# PET_Diag_Clip.net
KiCad netlist of a schematic drawn in EAGLE
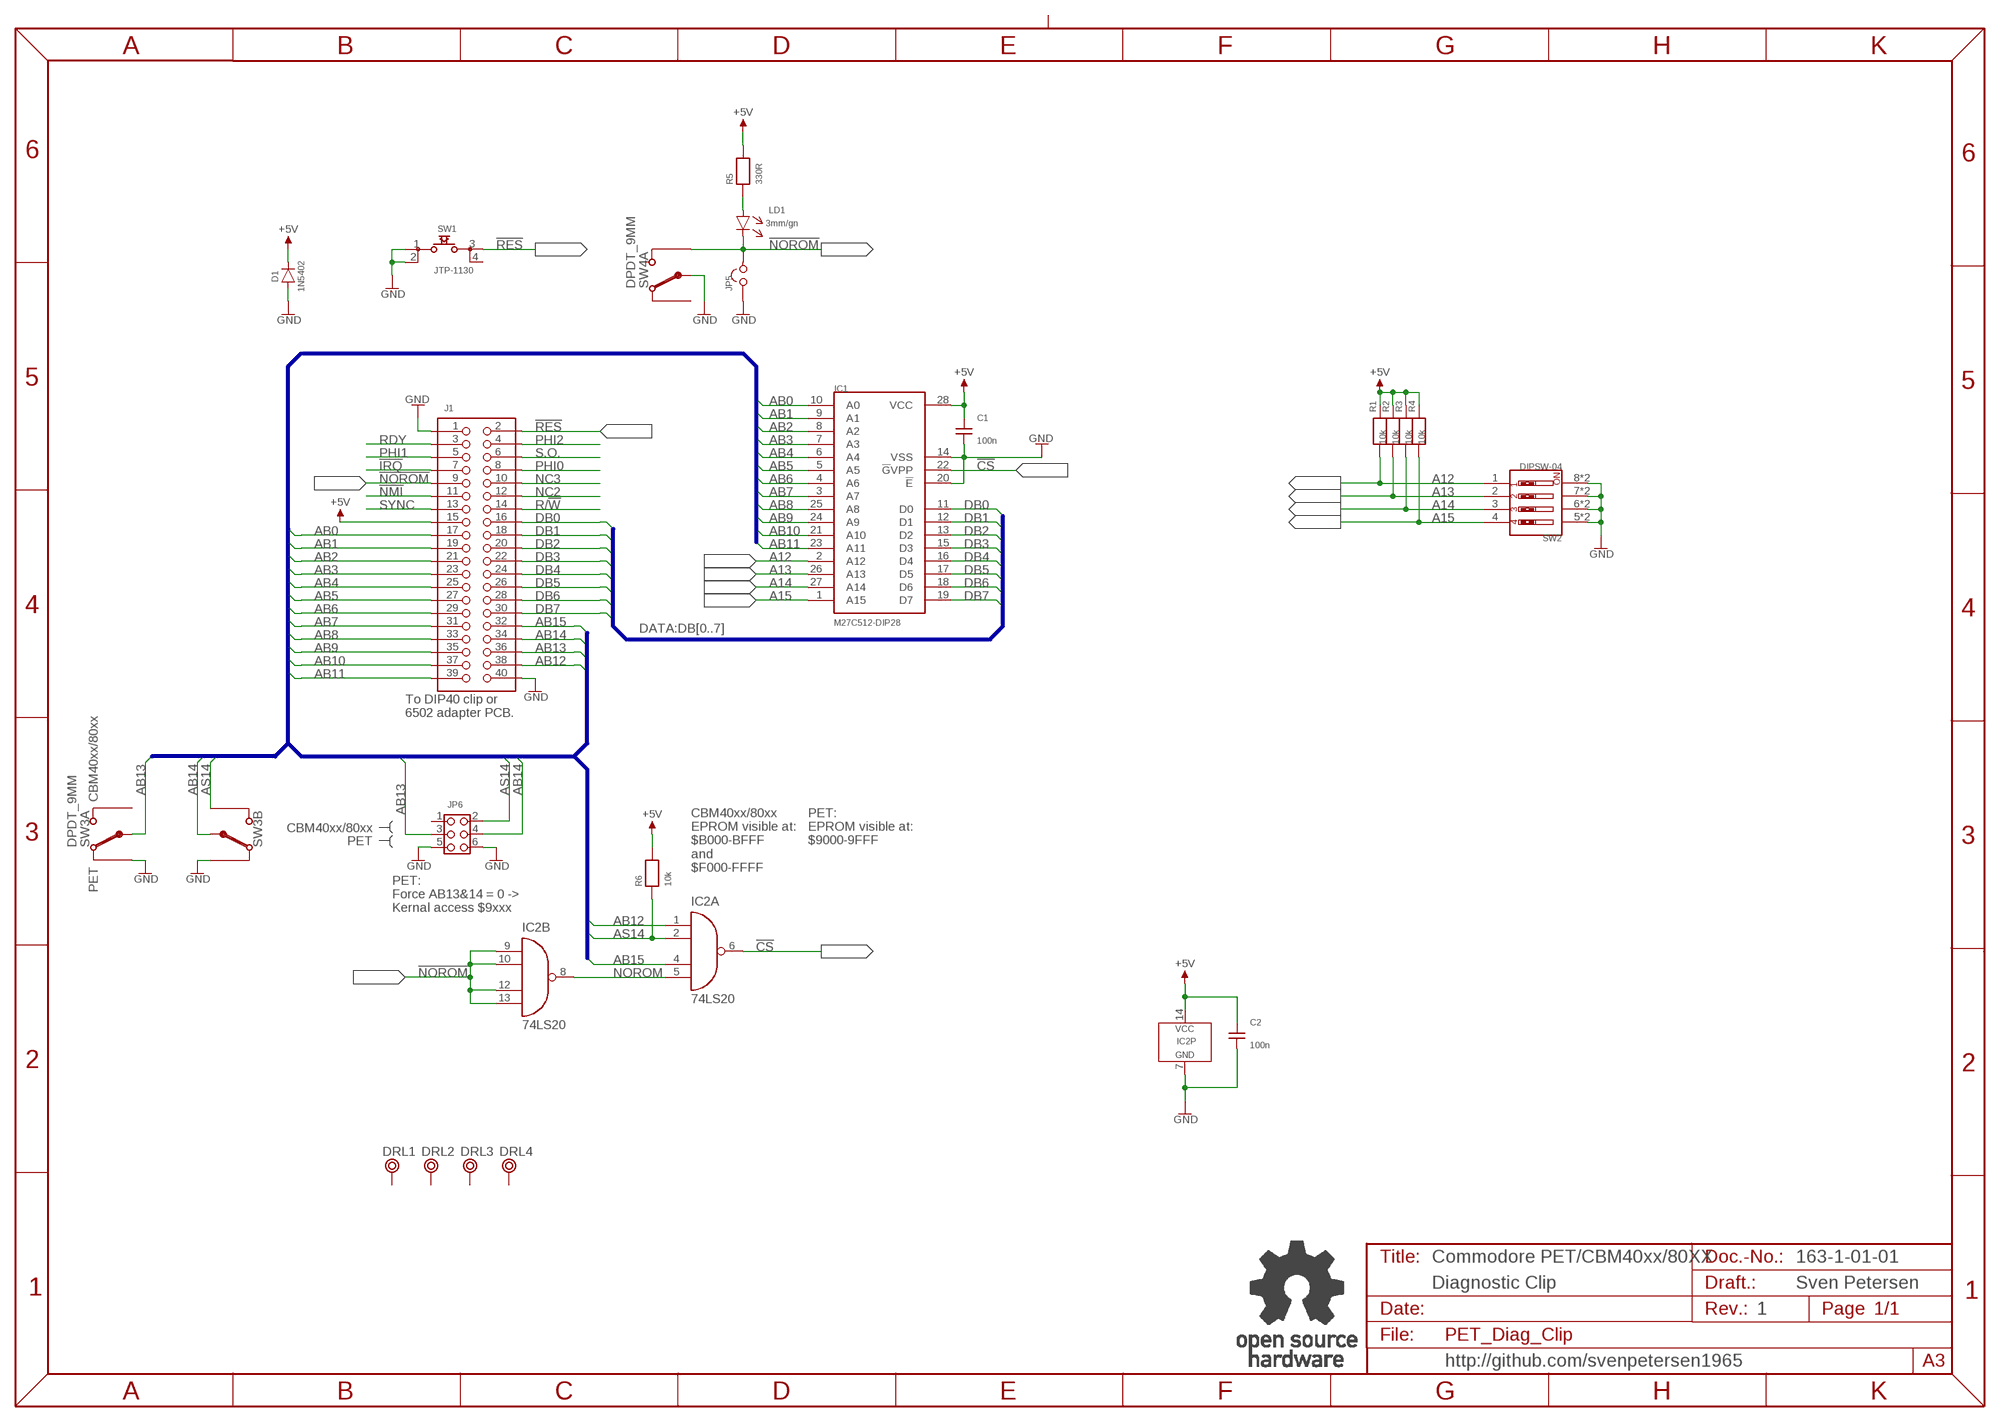
[diagram p0: schematic, sheet 1]

(export (version "E")
  (design (tool "Eeschema 10.0.6"))
  (components
    (comp (ref "C1")
      (value "100n")
      (footprint "eagle-import:C-2,5")
      (libsource (lib "eagle-import") (part "CAP01"))
    )
    (comp (ref "C2")
      (value "100n")
      (footprint "eagle-import:C-2,5")
      (libsource (lib "eagle-import") (part "CAP01"))
    )
    (comp (ref "D1")
      (value "1N5402")
      (footprint "eagle-import:DO-201")
      (libsource (lib "eagle-import") (part "1N5402"))
    )
    (comp (ref "DRL1")
      (value "BOHR3,5")
      (footprint "eagle-import:BOHR3,5")
      (libsource (lib "eagle-import") (part "BOHR3,5"))
    )
    (comp (ref "DRL2")
      (value "BOHR3,5")
      (footprint "eagle-import:BOHR3,5")
      (libsource (lib "eagle-import") (part "BOHR3,5"))
    )
    (comp (ref "DRL3")
      (value "BOHR3,5")
      (footprint "eagle-import:BOHR3,5")
      (libsource (lib "eagle-import") (part "BOHR3,5"))
    )
    (comp (ref "DRL4")
      (value "BOHR3,5")
      (footprint "eagle-import:BOHR3,5")
      (libsource (lib "eagle-import") (part "BOHR3,5"))
    )
    (comp (ref "IC1")
      (value "M27C512-DIP28")
      (footprint "eagle-import:DIL28-6")
      (libsource (lib "eagle-import") (part "M27C512-DIP28"))
    )
    (comp (ref "IC2")
      (value "74LS20")
      (footprint "eagle-import:DIL-14")
      (libsource (lib "eagle-import") (part "7420N"))
    )
    (comp (ref "J1")
      (value "PINHD-2X20WV")
      (footprint "eagle-import:2X20WV")
      (libsource (lib "eagle-import") (part "PINHD-2X20WV"))
    )
    (comp (ref "JP5")
      (value "JUMPER")
      (footprint "eagle-import:1X02")
      (libsource (lib "eagle-import") (part "JUMPER"))
    )
    (comp (ref "JP6")
      (value "JUMPER2X3")
      (footprint "eagle-import:2X03")
      (libsource (lib "eagle-import") (part "JUMPER2X3"))
    )
    (comp (ref "LD1")
      (value "3mm/gn")
      (footprint "eagle-import:3MM")
      (libsource (lib "eagle-import") (part "3MM"))
    )
    (comp (ref "R1")
      (value "10k")
      (footprint "eagle-import:R-10")
      (libsource (lib "eagle-import") (part "RES04"))
    )
    (comp (ref "R2")
      (value "10k")
      (footprint "eagle-import:R-10")
      (libsource (lib "eagle-import") (part "RES04"))
    )
    (comp (ref "R3")
      (value "10k")
      (footprint "eagle-import:R-10")
      (libsource (lib "eagle-import") (part "RES04"))
    )
    (comp (ref "R4")
      (value "10k")
      (footprint "eagle-import:R-10")
      (libsource (lib "eagle-import") (part "RES04"))
    )
    (comp (ref "R5")
      (value "330R")
      (footprint "eagle-import:R-10")
      (libsource (lib "eagle-import") (part "RES04"))
    )
    (comp (ref "R6")
      (value "10k")
      (footprint "eagle-import:R-10")
      (libsource (lib "eagle-import") (part "RES04"))
    )
    (comp (ref "SW1")
      (value "JTP-1130")
      (footprint "eagle-import:JTP-1130")
      (libsource (lib "eagle-import") (part "JTP-1130"))
    )
    (comp (ref "SW2")
      (value "DIPSW-04")
      (footprint "eagle-import:DIPSW-04V-COMBI")
      (libsource (lib "eagle-import") (part "DIPSW-04"))
    )
    (comp (ref "SW3")
      (value "DPDT_9MM")
      (footprint "eagle-import:DPDT_9MM")
      (libsource (lib "eagle-import") (part "DPDT_9MM"))
    )
    (comp (ref "SW4")
      (value "DPDT_9MM")
      (footprint "eagle-import:DPDT_9MM")
      (libsource (lib "eagle-import") (part "DPDT_9MM"))
    )
    (comp (ref "U$13")
      (value "OPEN_SOURCE_HW")
      (footprint "eagle-import:OPENHW")
      (libsource (lib "eagle-import") (part "OPEN_SOURCE_HW"))
    )
  )
  (nets
    (net (code "9") (name "+5V") (class "Default")
      (node (ref "C1") (pin "2") (pinfunction "2_2") (pintype "passive"))
      (node (ref "C2") (pin "2") (pinfunction "2_2") (pintype "passive"))
      (node (ref "D1") (pin "K") (pinfunction "K_K") (pintype "passive"))
      (node (ref "IC1") (pin "28") (pinfunction "VCC_28") (pintype "power_in"))
      (node (ref "IC2") (pin "14") (pinfunction "VCC_14") (pintype "bidirectional"))
      (node (ref "J1") (pin "15") (pinfunction "15_15") (pintype "passive"))
      (node (ref "R1") (pin "1") (pinfunction "1_1") (pintype "passive"))
      (node (ref "R2") (pin "1") (pinfunction "1_1") (pintype "passive"))
      (node (ref "R3") (pin "1") (pinfunction "1_1") (pintype "passive"))
      (node (ref "R4") (pin "1") (pinfunction "1_1") (pintype "passive"))
      (node (ref "R5") (pin "2") (pinfunction "2_2") (pintype "passive"))
      (node (ref "R6") (pin "2") (pinfunction "2_2") (pintype "passive"))
    )
    (net (code "10") (name "/A12") (class "Default")
      (node (ref "IC1") (pin "2") (pinfunction "A12_2") (pintype "input"))
      (node (ref "R1") (pin "2") (pinfunction "2_2") (pintype "passive"))
      (node (ref "SW2") (pin "1") (pinfunction "1_1") (pintype "passive"))
    )
    (net (code "11") (name "/A13") (class "Default")
      (node (ref "IC1") (pin "26") (pinfunction "A13_26") (pintype "input"))
      (node (ref "R2") (pin "2") (pinfunction "2_2") (pintype "passive"))
      (node (ref "SW2") (pin "2") (pinfunction "2_2") (pintype "passive"))
    )
    (net (code "12") (name "/A14") (class "Default")
      (node (ref "IC1") (pin "27") (pinfunction "A14_27") (pintype "input"))
      (node (ref "R3") (pin "2") (pinfunction "2_2") (pintype "passive"))
      (node (ref "SW2") (pin "3") (pinfunction "3_3") (pintype "passive"))
    )
    (net (code "13") (name "/A15") (class "Default")
      (node (ref "IC1") (pin "1") (pinfunction "A15_1") (pintype "input"))
      (node (ref "R4") (pin "2") (pinfunction "2_2") (pintype "passive"))
      (node (ref "SW2") (pin "4") (pinfunction "4_4") (pintype "passive"))
    )
    (net (code "14") (name "/AB0") (class "Default")
      (node (ref "IC1") (pin "10") (pinfunction "A0_10") (pintype "input"))
      (node (ref "J1") (pin "17") (pinfunction "17_17") (pintype "passive"))
    )
    (net (code "15") (name "/AB1") (class "Default")
      (node (ref "IC1") (pin "9") (pinfunction "A1_9") (pintype "input"))
      (node (ref "J1") (pin "19") (pinfunction "19_19") (pintype "passive"))
    )
    (net (code "16") (name "/AB2") (class "Default")
      (node (ref "IC1") (pin "8") (pinfunction "A2_8") (pintype "input"))
      (node (ref "J1") (pin "21") (pinfunction "21_21") (pintype "passive"))
    )
    (net (code "17") (name "/AB3") (class "Default")
      (node (ref "IC1") (pin "7") (pinfunction "A3_7") (pintype "input"))
      (node (ref "J1") (pin "23") (pinfunction "23_23") (pintype "passive"))
    )
    (net (code "18") (name "/AB4") (class "Default")
      (node (ref "IC1") (pin "6") (pinfunction "A4_6") (pintype "input"))
      (node (ref "J1") (pin "25") (pinfunction "25_25") (pintype "passive"))
    )
    (net (code "19") (name "/AB5") (class "Default")
      (node (ref "IC1") (pin "5") (pinfunction "A5_5") (pintype "input"))
      (node (ref "J1") (pin "27") (pinfunction "27_27") (pintype "passive"))
    )
    (net (code "20") (name "/AB6") (class "Default")
      (node (ref "IC1") (pin "4") (pinfunction "A6_4") (pintype "input"))
      (node (ref "J1") (pin "29") (pinfunction "29_29") (pintype "passive"))
    )
    (net (code "21") (name "/AB7") (class "Default")
      (node (ref "IC1") (pin "3") (pinfunction "A7_3") (pintype "input"))
      (node (ref "J1") (pin "31") (pinfunction "31_31") (pintype "passive"))
    )
    (net (code "22") (name "/AB8") (class "Default")
      (node (ref "IC1") (pin "25") (pinfunction "A8_25") (pintype "input"))
      (node (ref "J1") (pin "33") (pinfunction "33_33") (pintype "passive"))
    )
    (net (code "23") (name "/AB9") (class "Default")
      (node (ref "IC1") (pin "24") (pinfunction "A9_24") (pintype "input"))
      (node (ref "J1") (pin "35") (pinfunction "35_35") (pintype "passive"))
    )
    (net (code "24") (name "/AB10") (class "Default")
      (node (ref "IC1") (pin "21") (pinfunction "A10_21") (pintype "input"))
      (node (ref "J1") (pin "37") (pinfunction "37_37") (pintype "passive"))
    )
    (net (code "25") (name "/AB11") (class "Default")
      (node (ref "IC1") (pin "23") (pinfunction "A11_23") (pintype "input"))
      (node (ref "J1") (pin "39") (pinfunction "39_39") (pintype "passive"))
    )
    (net (code "26") (name "/AB12") (class "Default")
      (node (ref "IC2") (pin "1") (pinfunction "I0_1") (pintype "input"))
      (node (ref "J1") (pin "38") (pinfunction "38_38") (pintype "passive"))
    )
    (net (code "27") (name "/AB13") (class "Default")
      (node (ref "J1") (pin "36") (pinfunction "36_36") (pintype "passive"))
      (node (ref "JP6") (pin "3") (pinfunction "3_3") (pintype "bidirectional"))
      (node (ref "SW3") (pin "2") (pinfunction "COM_2") (pintype "bidirectional"))
    )
    (net (code "28") (name "/AB14") (class "Default")
      (node (ref "J1") (pin "34") (pinfunction "34_34") (pintype "passive"))
      (node (ref "JP6") (pin "4") (pinfunction "4_4") (pintype "bidirectional"))
      (node (ref "SW3") (pin "5") (pinfunction "COM_5") (pintype "bidirectional"))
    )
    (net (code "29") (name "/AB15") (class "Default")
      (node (ref "IC2") (pin "4") (pinfunction "I2_4") (pintype "input"))
      (node (ref "J1") (pin "32") (pinfunction "32_32") (pintype "passive"))
    )
    (net (code "30") (name "/AS14") (class "Default")
      (node (ref "IC2") (pin "2") (pinfunction "I1_2") (pintype "input"))
      (node (ref "JP6") (pin "2") (pinfunction "2_2") (pintype "bidirectional"))
      (node (ref "R6") (pin "1") (pinfunction "1_1") (pintype "passive"))
      (node (ref "SW3") (pin "6") (pinfunction "UP_6") (pintype "bidirectional"))
    )
    (net (code "32") (name "/DB0") (class "Default")
      (node (ref "IC1") (pin "11") (pinfunction "D0_11") (pintype "bidirectional"))
      (node (ref "J1") (pin "16") (pinfunction "16_16") (pintype "passive"))
    )
    (net (code "33") (name "/DB1") (class "Default")
      (node (ref "IC1") (pin "12") (pinfunction "D1_12") (pintype "bidirectional"))
      (node (ref "J1") (pin "18") (pinfunction "18_18") (pintype "passive"))
    )
    (net (code "34") (name "/DB2") (class "Default")
      (node (ref "IC1") (pin "13") (pinfunction "D2_13") (pintype "bidirectional"))
      (node (ref "J1") (pin "20") (pinfunction "20_20") (pintype "passive"))
    )
    (net (code "35") (name "/DB3") (class "Default")
      (node (ref "IC1") (pin "15") (pinfunction "D3_15") (pintype "bidirectional"))
      (node (ref "J1") (pin "22") (pinfunction "22_22") (pintype "passive"))
    )
    (net (code "36") (name "/DB4") (class "Default")
      (node (ref "IC1") (pin "16") (pinfunction "D4_16") (pintype "bidirectional"))
      (node (ref "J1") (pin "24") (pinfunction "24_24") (pintype "passive"))
    )
    (net (code "37") (name "/DB5") (class "Default")
      (node (ref "IC1") (pin "17") (pinfunction "D5_17") (pintype "bidirectional"))
      (node (ref "J1") (pin "26") (pinfunction "26_26") (pintype "passive"))
    )
    (net (code "38") (name "/DB6") (class "Default")
      (node (ref "IC1") (pin "18") (pinfunction "D6_18") (pintype "bidirectional"))
      (node (ref "J1") (pin "28") (pinfunction "28_28") (pintype "passive"))
    )
    (net (code "39") (name "/DB7") (class "Default")
      (node (ref "IC1") (pin "19") (pinfunction "D7_19") (pintype "bidirectional"))
      (node (ref "J1") (pin "30") (pinfunction "30_30") (pintype "passive"))
    )
    (net (code "40") (name "/NC2") (class "Default")
      (node (ref "J1") (pin "12") (pinfunction "12_12") (pintype "passive"))
    )
    (net (code "41") (name "/NC3") (class "Default")
      (node (ref "J1") (pin "10") (pinfunction "10_10") (pintype "passive"))
    )
    (net (code "42") (name "/NOROM") (class "Default")
      (node (ref "IC2") (pin "5") (pinfunction "I3_5") (pintype "input"))
      (node (ref "IC2") (pin "8") (pinfunction "O_8") (pintype "output"))
    )
    (net (code "43") (name "/PHI0") (class "Default")
      (node (ref "J1") (pin "8") (pinfunction "8_8") (pintype "passive"))
    )
    (net (code "44") (name "/PHI1") (class "Default")
      (node (ref "J1") (pin "5") (pinfunction "5_5") (pintype "passive"))
    )
    (net (code "45") (name "/PHI2") (class "Default")
      (node (ref "J1") (pin "4") (pinfunction "4_4") (pintype "passive"))
    )
    (net (code "46") (name "/RDY") (class "Default")
      (node (ref "J1") (pin "3") (pinfunction "3_3") (pintype "passive"))
    )
    (net (code "47") (name "/R{slash}~{W}") (class "Default")
      (node (ref "J1") (pin "14") (pinfunction "14_14") (pintype "passive"))
    )
    (net (code "48") (name "/S.O.") (class "Default")
      (node (ref "J1") (pin "6") (pinfunction "6_6") (pintype "passive"))
    )
    (net (code "49") (name "/SYNC") (class "Default")
      (node (ref "J1") (pin "13") (pinfunction "13_13") (pintype "passive"))
    )
    (net (code "50") (name "/~{CS}") (class "Default")
      (node (ref "IC1") (pin "22") (pinfunction "~{G}VPP_22") (pintype "input"))
      (node (ref "IC2") (pin "6") (pinfunction "O_6") (pintype "output"))
    )
    (net (code "51") (name "/~{IRQ}") (class "Default")
      (node (ref "J1") (pin "7") (pinfunction "7_7") (pintype "passive"))
    )
    (net (code "52") (name "/~{NMI}") (class "Default")
      (node (ref "J1") (pin "11") (pinfunction "11_11") (pintype "passive"))
    )
    (net (code "53") (name "/~{NOROM}") (class "Default")
      (node (ref "IC2") (pin "10") (pinfunction "I1_10") (pintype "input"))
      (node (ref "IC2") (pin "12") (pinfunction "I2_12") (pintype "input"))
      (node (ref "IC2") (pin "13") (pinfunction "I3_13") (pintype "input"))
      (node (ref "IC2") (pin "9") (pinfunction "I0_9") (pintype "input"))
      (node (ref "J1") (pin "9") (pinfunction "9_9") (pintype "passive"))
      (node (ref "JP5") (pin "2") (pinfunction "2_2") (pintype "bidirectional"))
      (node (ref "LD1") (pin "C") (pinfunction "K_C") (pintype "bidirectional"))
      (node (ref "SW4") (pin "1") (pinfunction "UP_1") (pintype "bidirectional"))
    )
    (net (code "54") (name "/~{RES}") (class "Default")
      (node (ref "J1") (pin "2") (pinfunction "2_2") (pintype "passive"))
      (node (ref "SW1") (pin "3") (pinfunction "3_3") (pintype "passive"))
    )
    (net (code "55") (name "GND") (class "Default")
      (node (ref "C1") (pin "1") (pinfunction "1_1") (pintype "passive"))
      (node (ref "C2") (pin "1") (pinfunction "1_1") (pintype "passive"))
      (node (ref "D1") (pin "A") (pinfunction "A_A") (pintype "passive"))
      (node (ref "IC1") (pin "14") (pinfunction "VSS_14") (pintype "power_in"))
      (node (ref "IC1") (pin "20") (pinfunction "~{E}_20") (pintype "input"))
      (node (ref "IC2") (pin "7") (pinfunction "GND_7") (pintype "bidirectional"))
      (node (ref "J1") (pin "1") (pinfunction "1_1") (pintype "passive"))
      (node (ref "J1") (pin "40") (pinfunction "40_40") (pintype "passive"))
      (node (ref "JP5") (pin "1") (pinfunction "1_1") (pintype "bidirectional"))
      (node (ref "JP6") (pin "5") (pinfunction "5_5") (pintype "bidirectional"))
      (node (ref "JP6") (pin "6") (pinfunction "6_6") (pintype "bidirectional"))
      (node (ref "SW1") (pin "1") (pinfunction "1_1") (pintype "passive"))
      (node (ref "SW1") (pin "2") (pinfunction "2_2") (pintype "passive"))
      (node (ref "SW2") (pin "5") (pinfunction "5_5") (pintype "passive"))
      (node (ref "SW2") (pin "5A") (pinfunction "5_5A") (pintype "passive"))
      (node (ref "SW2") (pin "6") (pinfunction "6_6") (pintype "passive"))
      (node (ref "SW2") (pin "6A") (pinfunction "6_6A") (pintype "passive"))
      (node (ref "SW2") (pin "7") (pinfunction "7_7") (pintype "passive"))
      (node (ref "SW2") (pin "7A") (pinfunction "7_7A") (pintype "passive"))
      (node (ref "SW2") (pin "8") (pinfunction "8_8") (pintype "passive"))
      (node (ref "SW2") (pin "8A") (pinfunction "8_8A") (pintype "passive"))
      (node (ref "SW3") (pin "3") (pinfunction "DWN_3") (pintype "bidirectional"))
      (node (ref "SW3") (pin "4") (pinfunction "DWN_4") (pintype "bidirectional"))
      (node (ref "SW4") (pin "2") (pinfunction "COM_2") (pintype "bidirectional"))
    )
    (net (code "56") (name "Net-(LD1-PadA)") (class "Default")
      (node (ref "LD1") (pin "A") (pinfunction "A_A") (pintype "bidirectional"))
      (node (ref "R5") (pin "1") (pinfunction "1_1") (pintype "passive"))
    )
    (net (code "57") (name "unconnected-(DRL1-PadP$1)") (class "Default")
      (node (ref "DRL1") (pin "P$1") (pinfunction "P$1_P$1") (pintype "passive"))
    )
    (net (code "58") (name "unconnected-(DRL2-PadP$1)") (class "Default")
      (node (ref "DRL2") (pin "P$1") (pinfunction "P$1_P$1") (pintype "passive"))
    )
    (net (code "59") (name "unconnected-(DRL3-PadP$1)") (class "Default")
      (node (ref "DRL3") (pin "P$1") (pinfunction "P$1_P$1") (pintype "passive"))
    )
    (net (code "60") (name "unconnected-(DRL4-PadP$1)") (class "Default")
      (node (ref "DRL4") (pin "P$1") (pinfunction "P$1_P$1") (pintype "passive"))
    )
    (net (code "61") (name "unconnected-(JP6-Pad1)") (class "Default")
      (node (ref "JP6") (pin "1") (pinfunction "1_1") (pintype "bidirectional"))
    )
    (net (code "62") (name "unconnected-(SW1-Pad4)") (class "Default")
      (node (ref "SW1") (pin "4") (pinfunction "4_4") (pintype "passive"))
    )
    (net (code "63") (name "unconnected-(SW3A-UP-Pad1)") (class "Default")
      (node (ref "SW3") (pin "1") (pinfunction "UP_1") (pintype "bidirectional"))
    )
    (net (code "64") (name "unconnected-(SW4A-DWN-Pad3)") (class "Default")
      (node (ref "SW4") (pin "3") (pinfunction "DWN_3") (pintype "bidirectional"))
    )
  )
)
